# design.net
KiCad netlist of a schematic drawn in Altium Designer
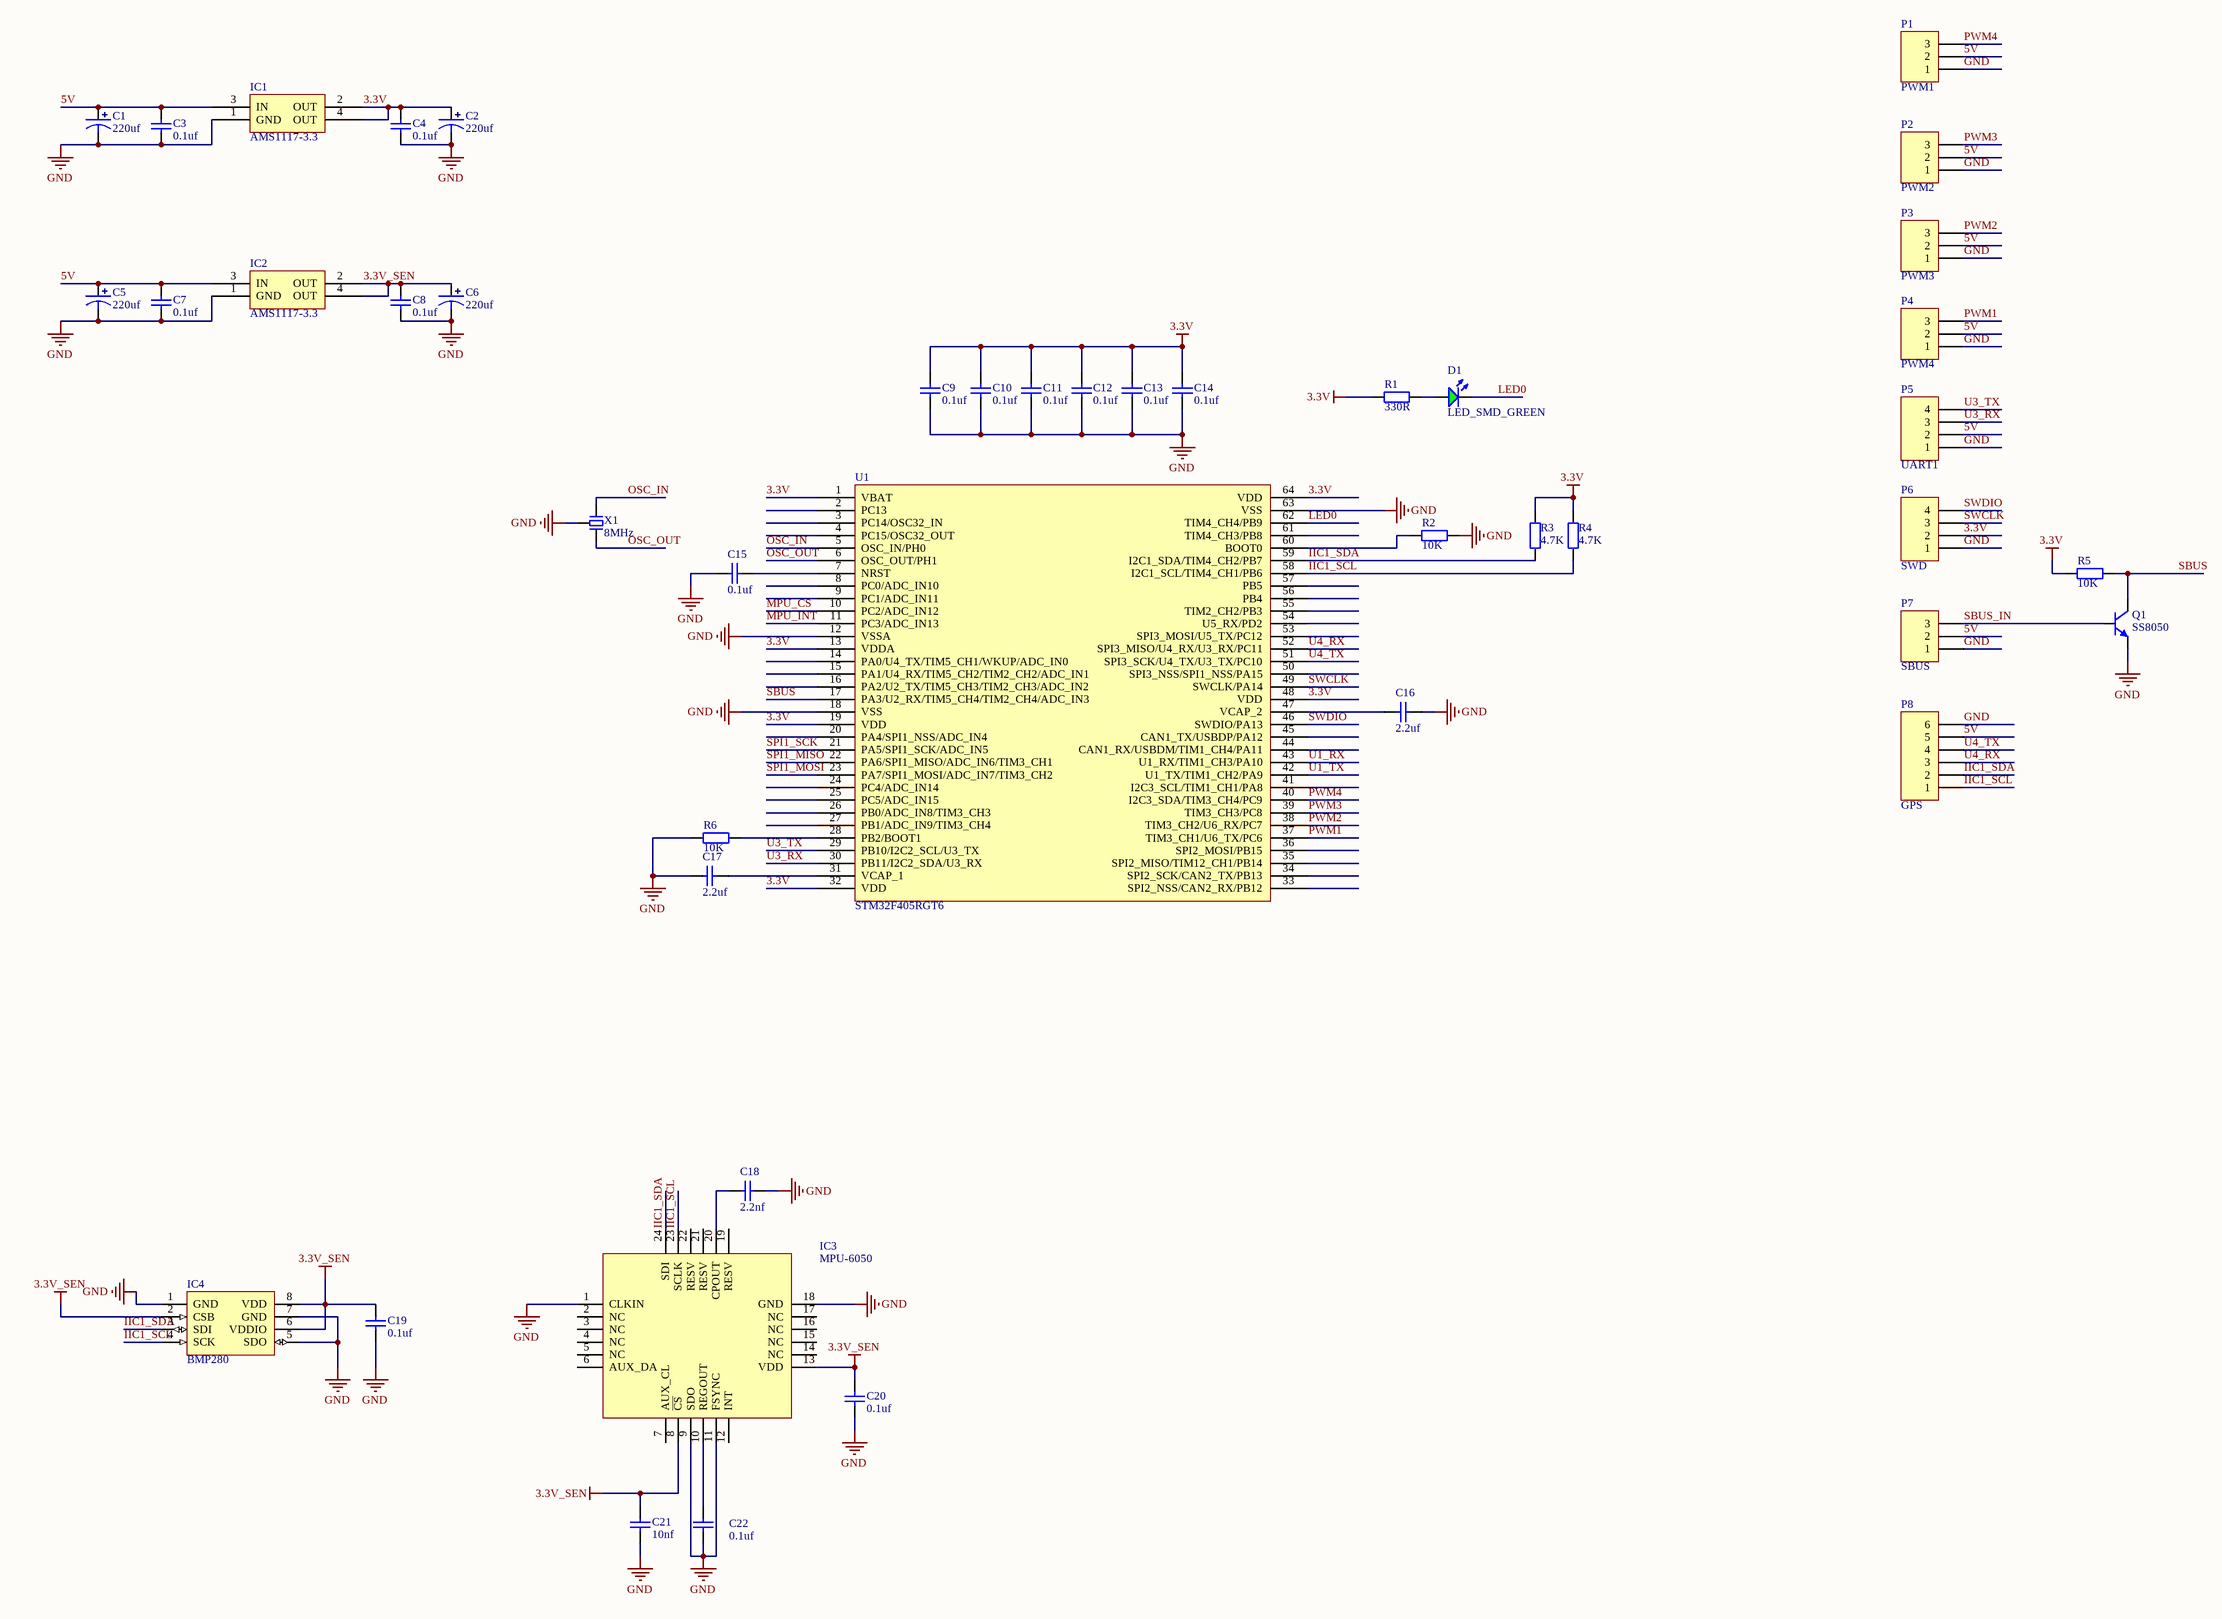
[diagram p0: 原理图.SchDoc]

(export (version "E")
  (design (tool "Eeschema 10.0.6"))
  (components
    (comp (ref "C1")
      (value "220uf")
      (footprint "CAPE_D_6.3X6.6X5.4")
      (description "贴片电解电容")
      (libsource (lib "Miscellaneous Base") (part "CAPE-SMD"))
    )
    (comp (ref "C2")
      (value "220uf")
      (footprint "CAPE_D_6.3X6.6X5.4")
      (description "贴片电解电容")
      (libsource (lib "Miscellaneous Base") (part "CAPE-SMD"))
    )
    (comp (ref "C3")
      (value "0.1uf")
      (footprint "Cap-0603")
      (description "贴片陶瓷电容")
      (libsource (lib "Miscellaneous Base") (part "CAP"))
    )
    (comp (ref "C4")
      (value "0.1uf")
      (footprint "Cap-0603")
      (description "贴片陶瓷电容")
      (libsource (lib "Miscellaneous Base") (part "CAP"))
    )
    (comp (ref "C5")
      (value "220uf")
      (footprint "CAPE_D_6.3X6.6X5.4")
      (description "贴片电解电容")
      (libsource (lib "Miscellaneous Base") (part "CAPE-SMD"))
    )
    (comp (ref "C6")
      (value "220uf")
      (footprint "CAPE_D_6.3X6.6X5.4")
      (description "贴片电解电容")
      (libsource (lib "Miscellaneous Base") (part "CAPE-SMD"))
    )
    (comp (ref "C7")
      (value "0.1uf")
      (footprint "Cap-0603")
      (description "贴片陶瓷电容")
      (libsource (lib "Miscellaneous Base") (part "CAP"))
    )
    (comp (ref "C8")
      (value "0.1uf")
      (footprint "Cap-0603")
      (description "贴片陶瓷电容")
      (libsource (lib "Miscellaneous Base") (part "CAP"))
    )
    (comp (ref "C9")
      (value "0.1uf")
      (footprint "Cap-0603")
      (description "贴片陶瓷电容")
      (libsource (lib "Miscellaneous Base") (part "CAP"))
    )
    (comp (ref "C10")
      (value "0.1uf")
      (footprint "Cap-0603")
      (description "贴片陶瓷电容")
      (libsource (lib "Miscellaneous Base") (part "CAP"))
    )
    (comp (ref "C11")
      (value "0.1uf")
      (footprint "Cap-0603")
      (description "贴片陶瓷电容")
      (libsource (lib "Miscellaneous Base") (part "CAP"))
    )
    (comp (ref "C12")
      (value "0.1uf")
      (footprint "Cap-0603")
      (description "贴片陶瓷电容")
      (libsource (lib "Miscellaneous Base") (part "CAP"))
    )
    (comp (ref "C13")
      (value "0.1uf")
      (footprint "Cap-0603")
      (description "贴片陶瓷电容")
      (libsource (lib "Miscellaneous Base") (part "CAP"))
    )
    (comp (ref "C14")
      (value "0.1uf")
      (footprint "Cap-0603")
      (description "贴片陶瓷电容")
      (libsource (lib "Miscellaneous Base") (part "CAP"))
    )
    (comp (ref "C15")
      (value "0.1uf")
      (footprint "Cap-0603")
      (description "贴片陶瓷电容")
      (libsource (lib "Miscellaneous Base") (part "CAP"))
    )
    (comp (ref "C16")
      (value "2.2uf")
      (footprint "Cap-0603")
      (description "贴片陶瓷电容")
      (libsource (lib "Miscellaneous Base") (part "CAP"))
    )
    (comp (ref "C17")
      (value "2.2uf")
      (footprint "Cap-0603")
      (description "贴片陶瓷电容")
      (libsource (lib "Miscellaneous Base") (part "CAP"))
    )
    (comp (ref "C18")
      (value "2.2nf")
      (footprint "Cap-0603")
      (description "贴片陶瓷电容")
      (libsource (lib "Miscellaneous Base") (part "CAP"))
    )
    (comp (ref "C19")
      (value "0.1uf")
      (footprint "Cap-0603")
      (description "贴片陶瓷电容")
      (libsource (lib "Miscellaneous Base") (part "CAP"))
    )
    (comp (ref "C20")
      (value "0.1uf")
      (footprint "Cap-0603")
      (description "贴片陶瓷电容")
      (libsource (lib "Miscellaneous Base") (part "CAP"))
    )
    (comp (ref "C21")
      (value "10nf")
      (footprint "Cap-0603")
      (description "贴片陶瓷电容")
      (libsource (lib "Miscellaneous Base") (part "CAP"))
    )
    (comp (ref "C22")
      (value "0.1uf")
      (footprint "Cap-0603")
      (description "贴片陶瓷电容")
      (libsource (lib "Miscellaneous Base") (part "CAP"))
    )
    (comp (ref "D1")
      (value "LED_SMD_GREEN")
      (footprint "LED_0603_G")
      (description "发光二极管")
      (libsource (lib "Miscellaneous Transistor") (part "LED_SMD_GREEN"))
    )
    (comp (ref "IC1")
      (value "AMS1117-3.3")
      (footprint "AMS1117")
      (libsource (lib "Miscellaneous PMIC") (part "AMS1117"))
    )
    (comp (ref "IC2")
      (value "AMS1117-3.3")
      (footprint "AMS1117")
      (libsource (lib "Miscellaneous PMIC") (part "AMS1117"))
    )
    (comp (ref "IC3")
      (value "MPU-6050")
      (footprint "QFN24 4X4_N")
      (description "传感器")
      (libsource (lib "ATKF405 V1.1") (part "MPU-6000"))
    )
    (comp (ref "IC4")
      (value "BMP280")
      (footprint "BMP280 LGA8")
      (description "气压传感器")
      (libsource (lib "ATKF405 V1.1") (part "BMP280"))
    )
    (comp (ref "P1")
      (value "PWM1")
      (footprint "Header 2.54X3")
      (libsource (lib "Miscellaneous Header") (part "Header_3"))
    )
    (comp (ref "P2")
      (value "PWM2")
      (footprint "Header 2.54X3")
      (libsource (lib "Miscellaneous Header") (part "Header_3"))
    )
    (comp (ref "P3")
      (value "PWM3")
      (footprint "Header 2.54X3")
      (libsource (lib "Miscellaneous Header") (part "Header_3"))
    )
    (comp (ref "P4")
      (value "PWM4")
      (footprint "Header 2.54X3")
      (libsource (lib "Miscellaneous Header") (part "Header_3"))
    )
    (comp (ref "P5")
      (value "UART1")
      (footprint "Header 2.54X4")
      (libsource (lib "Miscellaneous Header") (part "Header_4"))
    )
    (comp (ref "P6")
      (value "SWD")
      (footprint "Header 2.54X4")
      (libsource (lib "Miscellaneous Header") (part "Header_4"))
    )
    (comp (ref "P7")
      (value "SBUS")
      (footprint "Header 2.54X3")
      (libsource (lib "Miscellaneous Header") (part "Header_3"))
    )
    (comp (ref "P8")
      (value "GPS")
      (footprint "Header 2.54X6")
      (libsource (lib "Miscellaneous Header") (part "Header_6"))
    )
    (comp (ref "Q1")
      (value "SS8050")
      (footprint "SOT23-3L")
      (description "高频放大-NPN型")
      (fields (field (name "版权归属") "源创客"))
      (libsource (lib "ATKF405 V1.1") (part "8050-SMD"))
    )
    (comp (ref "R1")
      (value "330R")
      (footprint "Res-0603-M")
      (description "贴片电阻")
      (libsource (lib "") (part "RES_1"))
    )
    (comp (ref "R2")
      (value "10K")
      (footprint "Res-0603-M")
      (description "贴片电阻")
      (libsource (lib "Miscellaneous Base") (part "RES"))
    )
    (comp (ref "R3")
      (value "4.7K")
      (footprint "Res-0603-M")
      (description "贴片电阻")
      (libsource (lib "") (part "RES_2"))
    )
    (comp (ref "R4")
      (value "4.7K")
      (footprint "Res-0603-M")
      (description "贴片电阻")
      (libsource (lib "") (part "RES_2"))
    )
    (comp (ref "R5")
      (value "10K")
      (footprint "Res-0603")
      (description "贴片电阻")
      (libsource (lib "Miscellaneous Base") (part "RES"))
    )
    (comp (ref "R6")
      (value "10K")
      (footprint "Res-0603-M")
      (description "贴片电阻")
      (libsource (lib "Miscellaneous Base") (part "RES"))
    )
    (comp (ref "U1")
      (value "STM32F405RGT6")
      (footprint "LQFP64 10X10_L")
      (description "Flaah:256/RAM:48/IO:51")
      (libsource (lib "ATKF405 V1.1") (part "STM32F405RGT6"))
    )
    (comp (ref "X1")
      (value "8MHz")
      (footprint "XTAL-3215-3P")
      (description "3脚无源晶振")
      (fields (field (name "版权归属") "源创客"))
      (libsource (lib "ATKF405 V1.1") (part "XTAL-3P"))
    )
  )
  (nets
    (net (code "1") (name "/5V") (class "Default")
      (node (ref "C1") (pin "1") (pinfunction "1_1") (pintype "passive"))
      (node (ref "C3") (pin "2") (pinfunction "2_2") (pintype "passive"))
      (node (ref "C5") (pin "1") (pinfunction "1_1") (pintype "passive"))
      (node (ref "C7") (pin "2") (pinfunction "2_2") (pintype "passive"))
      (node (ref "IC1") (pin "3") (pinfunction "IN_3") (pintype "passive"))
      (node (ref "IC2") (pin "3") (pinfunction "IN_3") (pintype "passive"))
      (node (ref "P1") (pin "2") (pinfunction "2_2") (pintype "passive"))
      (node (ref "P2") (pin "2") (pinfunction "2_2") (pintype "passive"))
      (node (ref "P3") (pin "2") (pinfunction "2_2") (pintype "passive"))
      (node (ref "P4") (pin "2") (pinfunction "2_2") (pintype "passive"))
      (node (ref "P5") (pin "2") (pinfunction "2_2") (pintype "passive"))
      (node (ref "P7") (pin "2") (pinfunction "2_2") (pintype "passive"))
      (node (ref "P8") (pin "5") (pinfunction "5_5") (pintype "passive"))
    )
    (net (code "2") (name "/IIC1_SCL") (class "Default")
      (node (ref "IC3") (pin "23") (pinfunction "SCLK_23") (pintype "passive"))
      (node (ref "IC4") (pin "4") (pinfunction "SCK_4") (pintype "input"))
      (node (ref "P8") (pin "1") (pinfunction "1_1") (pintype "passive"))
      (node (ref "R4") (pin "1") (pinfunction "1_1") (pintype "passive"))
      (node (ref "U1") (pin "58") (pinfunction "I2C1_SCL/TIM4_CH1/PB6_58") (pintype "passive"))
    )
    (net (code "3") (name "/IIC1_SDA") (class "Default")
      (node (ref "IC3") (pin "24") (pinfunction "SDI_24") (pintype "passive"))
      (node (ref "IC4") (pin "3") (pinfunction "SDI_3") (pintype "bidirectional"))
      (node (ref "P8") (pin "2") (pinfunction "2_2") (pintype "passive"))
      (node (ref "R3") (pin "1") (pinfunction "1_1") (pintype "passive"))
      (node (ref "U1") (pin "59") (pinfunction "I2C1_SDA/TIM4_CH2/PB7_59") (pintype "passive"))
    )
    (net (code "4") (name "/LED0") (class "Default")
      (node (ref "D1") (pin "2") (pinfunction "K_2") (pintype "passive"))
      (node (ref "U1") (pin "62") (pinfunction "TIM4_CH4/PB9_62") (pintype "passive"))
    )
    (net (code "5") (name "/MPU_CS") (class "Default")
      (node (ref "U1") (pin "10") (pinfunction "PC2/ADC_IN12_10") (pintype "passive"))
    )
    (net (code "6") (name "/MPU_INT") (class "Default")
      (node (ref "U1") (pin "11") (pinfunction "PC3/ADC_IN13_11") (pintype "passive"))
    )
    (net (code "7") (name "/OSC_IN") (class "Default")
      (node (ref "U1") (pin "5") (pinfunction "OSC_IN/PH0_5") (pintype "passive"))
      (node (ref "X1") (pin "1") (pinfunction "1_1") (pintype "passive"))
    )
    (net (code "8") (name "/OSC_OUT") (class "Default")
      (node (ref "U1") (pin "6") (pinfunction "OSC_OUT/PH1_6") (pintype "passive"))
      (node (ref "X1") (pin "3") (pinfunction "3_3") (pintype "passive"))
    )
    (net (code "9") (name "/PWM1") (class "Default")
      (node (ref "P4") (pin "3") (pinfunction "3_3") (pintype "passive"))
      (node (ref "U1") (pin "37") (pinfunction "TIM3_CH1/U6_TX/PC6_37") (pintype "passive"))
    )
    (net (code "10") (name "/PWM2") (class "Default")
      (node (ref "P3") (pin "3") (pinfunction "3_3") (pintype "passive"))
      (node (ref "U1") (pin "38") (pinfunction "TIM3_CH2/U6_RX/PC7_38") (pintype "passive"))
    )
    (net (code "11") (name "/PWM3") (class "Default")
      (node (ref "P2") (pin "3") (pinfunction "3_3") (pintype "passive"))
      (node (ref "U1") (pin "39") (pinfunction "TIM3_CH3/PC8_39") (pintype "passive"))
    )
    (net (code "12") (name "/PWM4") (class "Default")
      (node (ref "P1") (pin "3") (pinfunction "3_3") (pintype "passive"))
      (node (ref "U1") (pin "40") (pinfunction "I2C3_SDA/TIM3_CH4/PC9_40") (pintype "passive"))
    )
    (net (code "13") (name "/SBUS") (class "Default")
      (node (ref "Q1") (pin "3") (pinfunction "C_3") (pintype "passive"))
      (node (ref "R5") (pin "2") (pinfunction "2_2") (pintype "passive"))
      (node (ref "U1") (pin "17") (pinfunction "PA3/U2_RX/TIM5_CH4/TIM2_CH4/ADC_IN3_17") (pintype "passive"))
    )
    (net (code "14") (name "/SBUS_IN") (class "Default")
      (node (ref "P7") (pin "3") (pinfunction "3_3") (pintype "passive"))
      (node (ref "Q1") (pin "1") (pinfunction "B_1") (pintype "passive"))
    )
    (net (code "15") (name "/SPI1_MISO") (class "Default")
      (node (ref "U1") (pin "22") (pinfunction "PA6/SPI1_MISO/ADC_IN6/TIM3_CH1_22") (pintype "passive"))
    )
    (net (code "16") (name "/SPI1_MOSI") (class "Default")
      (node (ref "U1") (pin "23") (pinfunction "PA7/SPI1_MOSI/ADC_IN7/TIM3_CH2_23") (pintype "passive"))
    )
    (net (code "17") (name "/SPI1_SCK") (class "Default")
      (node (ref "U1") (pin "21") (pinfunction "PA5/SPI1_SCK/ADC_IN5_21") (pintype "passive"))
    )
    (net (code "18") (name "/SWCLK") (class "Default")
      (node (ref "P6") (pin "3") (pinfunction "3_3") (pintype "passive"))
      (node (ref "U1") (pin "49") (pinfunction "SWCLK/PA14_49") (pintype "passive"))
    )
    (net (code "19") (name "/SWDIO") (class "Default")
      (node (ref "P6") (pin "4") (pinfunction "4_4") (pintype "passive"))
      (node (ref "U1") (pin "46") (pinfunction "SWDIO/PA13_46") (pintype "passive"))
    )
    (net (code "20") (name "/U1_RX") (class "Default")
      (node (ref "U1") (pin "43") (pinfunction "U1_RX/TIM1_CH3/PA10_43") (pintype "passive"))
    )
    (net (code "21") (name "/U1_TX") (class "Default")
      (node (ref "U1") (pin "42") (pinfunction "U1_TX/TIM1_CH2/PA9_42") (pintype "passive"))
    )
    (net (code "22") (name "/U3_RX") (class "Default")
      (node (ref "P5") (pin "3") (pinfunction "3_3") (pintype "passive"))
      (node (ref "U1") (pin "30") (pinfunction "PB11/I2C2_SDA/U3_RX_30") (pintype "passive"))
    )
    (net (code "23") (name "/U3_TX") (class "Default")
      (node (ref "P5") (pin "4") (pinfunction "4_4") (pintype "passive"))
      (node (ref "U1") (pin "29") (pinfunction "PB10/I2C2_SCL/U3_TX_29") (pintype "passive"))
    )
    (net (code "24") (name "/U4_RX") (class "Default")
      (node (ref "P8") (pin "3") (pinfunction "3_3") (pintype "passive"))
      (node (ref "U1") (pin "52") (pinfunction "SPI3_MISO/U4_RX/U3_RX/PC11_52") (pintype "passive"))
    )
    (net (code "25") (name "/U4_TX") (class "Default")
      (node (ref "P8") (pin "4") (pinfunction "4_4") (pintype "passive"))
      (node (ref "U1") (pin "51") (pinfunction "SPI3_SCK/U4_TX/U3_TX/PC10_51") (pintype "passive"))
    )
    (net (code "26") (name "3.3V") (class "Default")
      (node (ref "C10") (pin "2") (pinfunction "2_2") (pintype "passive"))
      (node (ref "C11") (pin "2") (pinfunction "2_2") (pintype "passive"))
      (node (ref "C12") (pin "2") (pinfunction "2_2") (pintype "passive"))
      (node (ref "C13") (pin "2") (pinfunction "2_2") (pintype "passive"))
      (node (ref "C14") (pin "2") (pinfunction "2_2") (pintype "passive"))
      (node (ref "C2") (pin "1") (pinfunction "1_1") (pintype "passive"))
      (node (ref "C4") (pin "2") (pinfunction "2_2") (pintype "passive"))
      (node (ref "C9") (pin "2") (pinfunction "2_2") (pintype "passive"))
      (node (ref "IC1") (pin "2") (pinfunction "OUT_2") (pintype "passive"))
      (node (ref "IC1") (pin "4") (pinfunction "OUT_4") (pintype "passive"))
      (node (ref "P6") (pin "2") (pinfunction "2_2") (pintype "passive"))
      (node (ref "R1") (pin "2") (pinfunction "2_2") (pintype "passive"))
      (node (ref "R3") (pin "2") (pinfunction "2_2") (pintype "passive"))
      (node (ref "R4") (pin "2") (pinfunction "2_2") (pintype "passive"))
      (node (ref "R5") (pin "1") (pinfunction "1_1") (pintype "passive"))
      (node (ref "U1") (pin "1") (pinfunction "VBAT_1") (pintype "passive"))
      (node (ref "U1") (pin "13") (pinfunction "VDDA_13") (pintype "passive"))
      (node (ref "U1") (pin "19") (pinfunction "VDD_19") (pintype "passive"))
      (node (ref "U1") (pin "32") (pinfunction "VDD_32") (pintype "passive"))
      (node (ref "U1") (pin "48") (pinfunction "VDD_48") (pintype "passive"))
      (node (ref "U1") (pin "64") (pinfunction "VDD_64") (pintype "passive"))
    )
    (net (code "27") (name "3.3V_SEN") (class "Default")
      (node (ref "C19") (pin "2") (pinfunction "2_2") (pintype "passive"))
      (node (ref "C20") (pin "2") (pinfunction "2_2") (pintype "passive"))
      (node (ref "C21") (pin "2") (pinfunction "2_2") (pintype "passive"))
      (node (ref "C6") (pin "1") (pinfunction "1_1") (pintype "passive"))
      (node (ref "C8") (pin "2") (pinfunction "2_2") (pintype "passive"))
      (node (ref "IC2") (pin "2") (pinfunction "OUT_2") (pintype "passive"))
      (node (ref "IC2") (pin "4") (pinfunction "OUT_4") (pintype "passive"))
      (node (ref "IC3") (pin "13") (pinfunction "VDD_13") (pintype "passive"))
      (node (ref "IC3") (pin "8") (pinfunction "~{CS}_8") (pintype "passive"))
      (node (ref "IC4") (pin "2") (pinfunction "CSB_2") (pintype "input"))
      (node (ref "IC4") (pin "6") (pinfunction "VDDIO_6") (pintype "power_in"))
      (node (ref "IC4") (pin "8") (pinfunction "VDD_8") (pintype "power_in"))
    )
    (net (code "28") (name "GND") (class "Default")
      (node (ref "C1") (pin "2") (pinfunction "2_2") (pintype "passive"))
      (node (ref "C10") (pin "1") (pinfunction "1_1") (pintype "passive"))
      (node (ref "C11") (pin "1") (pinfunction "1_1") (pintype "passive"))
      (node (ref "C12") (pin "1") (pinfunction "1_1") (pintype "passive"))
      (node (ref "C13") (pin "1") (pinfunction "1_1") (pintype "passive"))
      (node (ref "C14") (pin "1") (pinfunction "1_1") (pintype "passive"))
      (node (ref "C15") (pin "1") (pinfunction "1_1") (pintype "passive"))
      (node (ref "C16") (pin "2") (pinfunction "2_2") (pintype "passive"))
      (node (ref "C17") (pin "1") (pinfunction "1_1") (pintype "passive"))
      (node (ref "C18") (pin "2") (pinfunction "2_2") (pintype "passive"))
      (node (ref "C19") (pin "1") (pinfunction "1_1") (pintype "passive"))
      (node (ref "C2") (pin "2") (pinfunction "2_2") (pintype "passive"))
      (node (ref "C20") (pin "1") (pinfunction "1_1") (pintype "passive"))
      (node (ref "C21") (pin "1") (pinfunction "1_1") (pintype "passive"))
      (node (ref "C22") (pin "1") (pinfunction "1_1") (pintype "passive"))
      (node (ref "C3") (pin "1") (pinfunction "1_1") (pintype "passive"))
      (node (ref "C4") (pin "1") (pinfunction "1_1") (pintype "passive"))
      (node (ref "C5") (pin "2") (pinfunction "2_2") (pintype "passive"))
      (node (ref "C6") (pin "2") (pinfunction "2_2") (pintype "passive"))
      (node (ref "C7") (pin "1") (pinfunction "1_1") (pintype "passive"))
      (node (ref "C8") (pin "1") (pinfunction "1_1") (pintype "passive"))
      (node (ref "C9") (pin "1") (pinfunction "1_1") (pintype "passive"))
      (node (ref "IC1") (pin "1") (pinfunction "GND_1") (pintype "passive"))
      (node (ref "IC2") (pin "1") (pinfunction "GND_1") (pintype "passive"))
      (node (ref "IC3") (pin "1") (pinfunction "CLKIN_1") (pintype "passive"))
      (node (ref "IC3") (pin "11") (pinfunction "FSYNC_11") (pintype "passive"))
      (node (ref "IC3") (pin "18") (pinfunction "GND_18") (pintype "passive"))
      (node (ref "IC3") (pin "9") (pinfunction "SDO_9") (pintype "passive"))
      (node (ref "IC4") (pin "1") (pinfunction "GND_1") (pintype "passive"))
      (node (ref "IC4") (pin "5") (pinfunction "SDO_5") (pintype "bidirectional"))
      (node (ref "IC4") (pin "7") (pinfunction "GND_7") (pintype "power_in"))
      (node (ref "P1") (pin "1") (pinfunction "1_1") (pintype "passive"))
      (node (ref "P2") (pin "1") (pinfunction "1_1") (pintype "passive"))
      (node (ref "P3") (pin "1") (pinfunction "1_1") (pintype "passive"))
      (node (ref "P4") (pin "1") (pinfunction "1_1") (pintype "passive"))
      (node (ref "P5") (pin "1") (pinfunction "1_1") (pintype "passive"))
      (node (ref "P6") (pin "1") (pinfunction "1_1") (pintype "passive"))
      (node (ref "P7") (pin "1") (pinfunction "1_1") (pintype "passive"))
      (node (ref "P8") (pin "6") (pinfunction "6_6") (pintype "passive"))
      (node (ref "Q1") (pin "2") (pinfunction "E_2") (pintype "passive"))
      (node (ref "R2") (pin "2") (pinfunction "2_2") (pintype "passive"))
      (node (ref "R6") (pin "1") (pinfunction "1_1") (pintype "passive"))
      (node (ref "U1") (pin "12") (pinfunction "VSSA_12") (pintype "passive"))
      (node (ref "U1") (pin "18") (pinfunction "VSS_18") (pintype "passive"))
      (node (ref "U1") (pin "63") (pinfunction "VSS_63") (pintype "passive"))
      (node (ref "X1") (pin "2") (pinfunction "2_2") (pintype "passive"))
    )
    (net (code "29") (name "Net-(D1-A)") (class "Default")
      (node (ref "D1") (pin "1") (pinfunction "A_1") (pintype "passive"))
      (node (ref "R1") (pin "1") (pinfunction "1_1") (pintype "passive"))
    )
    (net (code "30") (name "Net-(IC3-CPOUT)") (class "Default")
      (node (ref "C18") (pin "1") (pinfunction "1_1") (pintype "passive"))
      (node (ref "IC3") (pin "20") (pinfunction "CPOUT_20") (pintype "passive"))
    )
    (net (code "31") (name "Net-(IC3-REGOUT)") (class "Default")
      (node (ref "C22") (pin "2") (pinfunction "2_2") (pintype "passive"))
      (node (ref "IC3") (pin "10") (pinfunction "REGOUT_10") (pintype "passive"))
    )
    (net (code "32") (name "Net-(U1-BOOT0)") (class "Default")
      (node (ref "R2") (pin "1") (pinfunction "1_1") (pintype "passive"))
      (node (ref "U1") (pin "60") (pinfunction "BOOT0_60") (pintype "passive"))
    )
    (net (code "33") (name "Net-(U1-NRST)") (class "Default")
      (node (ref "C15") (pin "2") (pinfunction "2_2") (pintype "passive"))
      (node (ref "U1") (pin "7") (pinfunction "NRST_7") (pintype "passive"))
    )
    (net (code "34") (name "Net-(U1-PB2{slash}BOOT1)") (class "Default")
      (node (ref "R6") (pin "2") (pinfunction "2_2") (pintype "passive"))
      (node (ref "U1") (pin "28") (pinfunction "PB2/BOOT1_28") (pintype "passive"))
    )
    (net (code "35") (name "Net-(U1-VCAP_1)") (class "Default")
      (node (ref "C17") (pin "2") (pinfunction "2_2") (pintype "passive"))
      (node (ref "U1") (pin "31") (pinfunction "VCAP_1_31") (pintype "passive"))
    )
    (net (code "36") (name "Net-(U1-VCAP_2)") (class "Default")
      (node (ref "C16") (pin "1") (pinfunction "1_1") (pintype "passive"))
      (node (ref "U1") (pin "47") (pinfunction "VCAP_2_47") (pintype "passive"))
    )
    (net (code "37") (name "unconnected-(IC3-AUX_CL-Pad7)") (class "Default")
      (node (ref "IC3") (pin "7") (pinfunction "AUX_CL_7") (pintype "passive"))
    )
    (net (code "38") (name "unconnected-(IC3-AUX_DA-Pad6)") (class "Default")
      (node (ref "IC3") (pin "6") (pinfunction "AUX_DA_6") (pintype "passive"))
    )
    (net (code "39") (name "unconnected-(IC3-INT-Pad12)") (class "Default")
      (node (ref "IC3") (pin "12") (pinfunction "INT_12") (pintype "passive"))
    )
    (net (code "40") (name "unconnected-(IC3-NC-Pad2)") (class "Default")
      (node (ref "IC3") (pin "2") (pinfunction "NC_2") (pintype "passive"))
    )
    (net (code "41") (name "unconnected-(IC3-NC-Pad3)") (class "Default")
      (node (ref "IC3") (pin "3") (pinfunction "NC_3") (pintype "passive"))
    )
    (net (code "42") (name "unconnected-(IC3-NC-Pad4)") (class "Default")
      (node (ref "IC3") (pin "4") (pinfunction "NC_4") (pintype "passive"))
    )
    (net (code "43") (name "unconnected-(IC3-NC-Pad5)") (class "Default")
      (node (ref "IC3") (pin "5") (pinfunction "NC_5") (pintype "passive"))
    )
    (net (code "44") (name "unconnected-(IC3-NC-Pad14)") (class "Default")
      (node (ref "IC3") (pin "14") (pinfunction "NC_14") (pintype "passive"))
    )
    (net (code "45") (name "unconnected-(IC3-NC-Pad15)") (class "Default")
      (node (ref "IC3") (pin "15") (pinfunction "NC_15") (pintype "passive"))
    )
    (net (code "46") (name "unconnected-(IC3-NC-Pad16)") (class "Default")
      (node (ref "IC3") (pin "16") (pinfunction "NC_16") (pintype "passive"))
    )
    (net (code "47") (name "unconnected-(IC3-NC-Pad17)") (class "Default")
      (node (ref "IC3") (pin "17") (pinfunction "NC_17") (pintype "passive"))
    )
    (net (code "48") (name "unconnected-(IC3-RESV-Pad19)") (class "Default")
      (node (ref "IC3") (pin "19") (pinfunction "RESV_19") (pintype "passive"))
    )
    (net (code "49") (name "unconnected-(IC3-RESV-Pad21)") (class "Default")
      (node (ref "IC3") (pin "21") (pinfunction "RESV_21") (pintype "passive"))
    )
    (net (code "50") (name "unconnected-(IC3-RESV-Pad22)") (class "Default")
      (node (ref "IC3") (pin "22") (pinfunction "RESV_22") (pintype "passive"))
    )
    (net (code "51") (name "unconnected-(U1-CAN1_RX{slash}USBDM{slash}TIM1_CH4{slash}PA11-Pad44)") (class "Default")
      (node (ref "U1") (pin "44") (pinfunction "CAN1_RX/USBDM/TIM1_CH4/PA11_44") (pintype "passive"))
    )
    (net (code "52") (name "unconnected-(U1-CAN1_TX{slash}USBDP{slash}PA12-Pad45)") (class "Default")
      (node (ref "U1") (pin "45") (pinfunction "CAN1_TX/USBDP/PA12_45") (pintype "passive"))
    )
    (net (code "53") (name "unconnected-(U1-I2C3_SCL{slash}TIM1_CH1{slash}PA8-Pad41)") (class "Default")
      (node (ref "U1") (pin "41") (pinfunction "I2C3_SCL/TIM1_CH1/PA8_41") (pintype "passive"))
    )
    (net (code "54") (name "unconnected-(U1-PA0{slash}U4_TX{slash}TIM5_CH1{slash}WKUP{slash}ADC_IN0-Pad14)") (class "Default")
      (node (ref "U1") (pin "14") (pinfunction "PA0/U4_TX/TIM5_CH1/WKUP/ADC_IN0_14") (pintype "passive"))
    )
    (net (code "55") (name "unconnected-(U1-PA1{slash}U4_RX{slash}TIM5_CH2{slash}TIM2_CH2{slash}ADC_IN1-Pad15)") (class "Default")
      (node (ref "U1") (pin "15") (pinfunction "PA1/U4_RX/TIM5_CH2/TIM2_CH2/ADC_IN1_15") (pintype "passive"))
    )
    (net (code "56") (name "unconnected-(U1-PA2{slash}U2_TX{slash}TIM5_CH3{slash}TIM2_CH3{slash}ADC_IN2-Pad16)") (class "Default")
      (node (ref "U1") (pin "16") (pinfunction "PA2/U2_TX/TIM5_CH3/TIM2_CH3/ADC_IN2_16") (pintype "passive"))
    )
    (net (code "57") (name "unconnected-(U1-PA4{slash}SPI1_NSS{slash}ADC_IN4-Pad20)") (class "Default")
      (node (ref "U1") (pin "20") (pinfunction "PA4/SPI1_NSS/ADC_IN4_20") (pintype "passive"))
    )
    (net (code "58") (name "unconnected-(U1-PB0{slash}ADC_IN8{slash}TIM3_CH3-Pad26)") (class "Default")
      (node (ref "U1") (pin "26") (pinfunction "PB0/ADC_IN8/TIM3_CH3_26") (pintype "passive"))
    )
    (net (code "59") (name "unconnected-(U1-PB1{slash}ADC_IN9{slash}TIM3_CH4-Pad27)") (class "Default")
      (node (ref "U1") (pin "27") (pinfunction "PB1/ADC_IN9/TIM3_CH4_27") (pintype "passive"))
    )
    (net (code "60") (name "unconnected-(U1-PB4-Pad56)") (class "Default")
      (node (ref "U1") (pin "56") (pinfunction "PB4_56") (pintype "passive"))
    )
    (net (code "61") (name "unconnected-(U1-PB5-Pad57)") (class "Default")
      (node (ref "U1") (pin "57") (pinfunction "PB5_57") (pintype "passive"))
    )
    (net (code "62") (name "unconnected-(U1-PC0{slash}ADC_IN10-Pad8)") (class "Default")
      (node (ref "U1") (pin "8") (pinfunction "PC0/ADC_IN10_8") (pintype "passive"))
    )
    (net (code "63") (name "unconnected-(U1-PC1{slash}ADC_IN11-Pad9)") (class "Default")
      (node (ref "U1") (pin "9") (pinfunction "PC1/ADC_IN11_9") (pintype "passive"))
    )
    (net (code "64") (name "unconnected-(U1-PC4{slash}ADC_IN14-Pad24)") (class "Default")
      (node (ref "U1") (pin "24") (pinfunction "PC4/ADC_IN14_24") (pintype "passive"))
    )
    (net (code "65") (name "unconnected-(U1-PC5{slash}ADC_IN15-Pad25)") (class "Default")
      (node (ref "U1") (pin "25") (pinfunction "PC5/ADC_IN15_25") (pintype "passive"))
    )
    (net (code "66") (name "unconnected-(U1-PC13-Pad2)") (class "Default")
      (node (ref "U1") (pin "2") (pinfunction "PC13_2") (pintype "passive"))
    )
    (net (code "67") (name "unconnected-(U1-PC14{slash}OSC32_IN-Pad3)") (class "Default")
      (node (ref "U1") (pin "3") (pinfunction "PC14/OSC32_IN_3") (pintype "passive"))
    )
    (net (code "68") (name "unconnected-(U1-PC15{slash}OSC32_OUT-Pad4)") (class "Default")
      (node (ref "U1") (pin "4") (pinfunction "PC15/OSC32_OUT_4") (pintype "passive"))
    )
    (net (code "69") (name "unconnected-(U1-SPI2_MISO{slash}TIM12_CH1{slash}PB14-Pad35)") (class "Default")
      (node (ref "U1") (pin "35") (pinfunction "SPI2_MISO/TIM12_CH1/PB14_35") (pintype "passive"))
    )
    (net (code "70") (name "unconnected-(U1-SPI2_MOSI{slash}PB15-Pad36)") (class "Default")
      (node (ref "U1") (pin "36") (pinfunction "SPI2_MOSI/PB15_36") (pintype "passive"))
    )
    (net (code "71") (name "unconnected-(U1-SPI2_NSS{slash}CAN2_RX{slash}PB12-Pad33)") (class "Default")
      (node (ref "U1") (pin "33") (pinfunction "SPI2_NSS/CAN2_RX/PB12_33") (pintype "passive"))
    )
    (net (code "72") (name "unconnected-(U1-SPI2_SCK{slash}CAN2_TX{slash}PB13-Pad34)") (class "Default")
      (node (ref "U1") (pin "34") (pinfunction "SPI2_SCK/CAN2_TX/PB13_34") (pintype "passive"))
    )
    (net (code "73") (name "unconnected-(U1-SPI3_MOSI{slash}U5_TX{slash}PC12-Pad53)") (class "Default")
      (node (ref "U1") (pin "53") (pinfunction "SPI3_MOSI/U5_TX/PC12_53") (pintype "passive"))
    )
    (net (code "74") (name "unconnected-(U1-SPI3_NSS{slash}SPI1_NSS{slash}PA15-Pad50)") (class "Default")
      (node (ref "U1") (pin "50") (pinfunction "SPI3_NSS/SPI1_NSS/PA15_50") (pintype "passive"))
    )
    (net (code "75") (name "unconnected-(U1-TIM2_CH2{slash}PB3-Pad55)") (class "Default")
      (node (ref "U1") (pin "55") (pinfunction "TIM2_CH2/PB3_55") (pintype "passive"))
    )
    (net (code "76") (name "unconnected-(U1-TIM4_CH3{slash}PB8-Pad61)") (class "Default")
      (node (ref "U1") (pin "61") (pinfunction "TIM4_CH3/PB8_61") (pintype "passive"))
    )
    (net (code "77") (name "unconnected-(U1-U5_RX{slash}PD2-Pad54)") (class "Default")
      (node (ref "U1") (pin "54") (pinfunction "U5_RX/PD2_54") (pintype "passive"))
    )
  )
)
